# Interface.net
KiCad netlist of a schematic drawn in Altium Designer
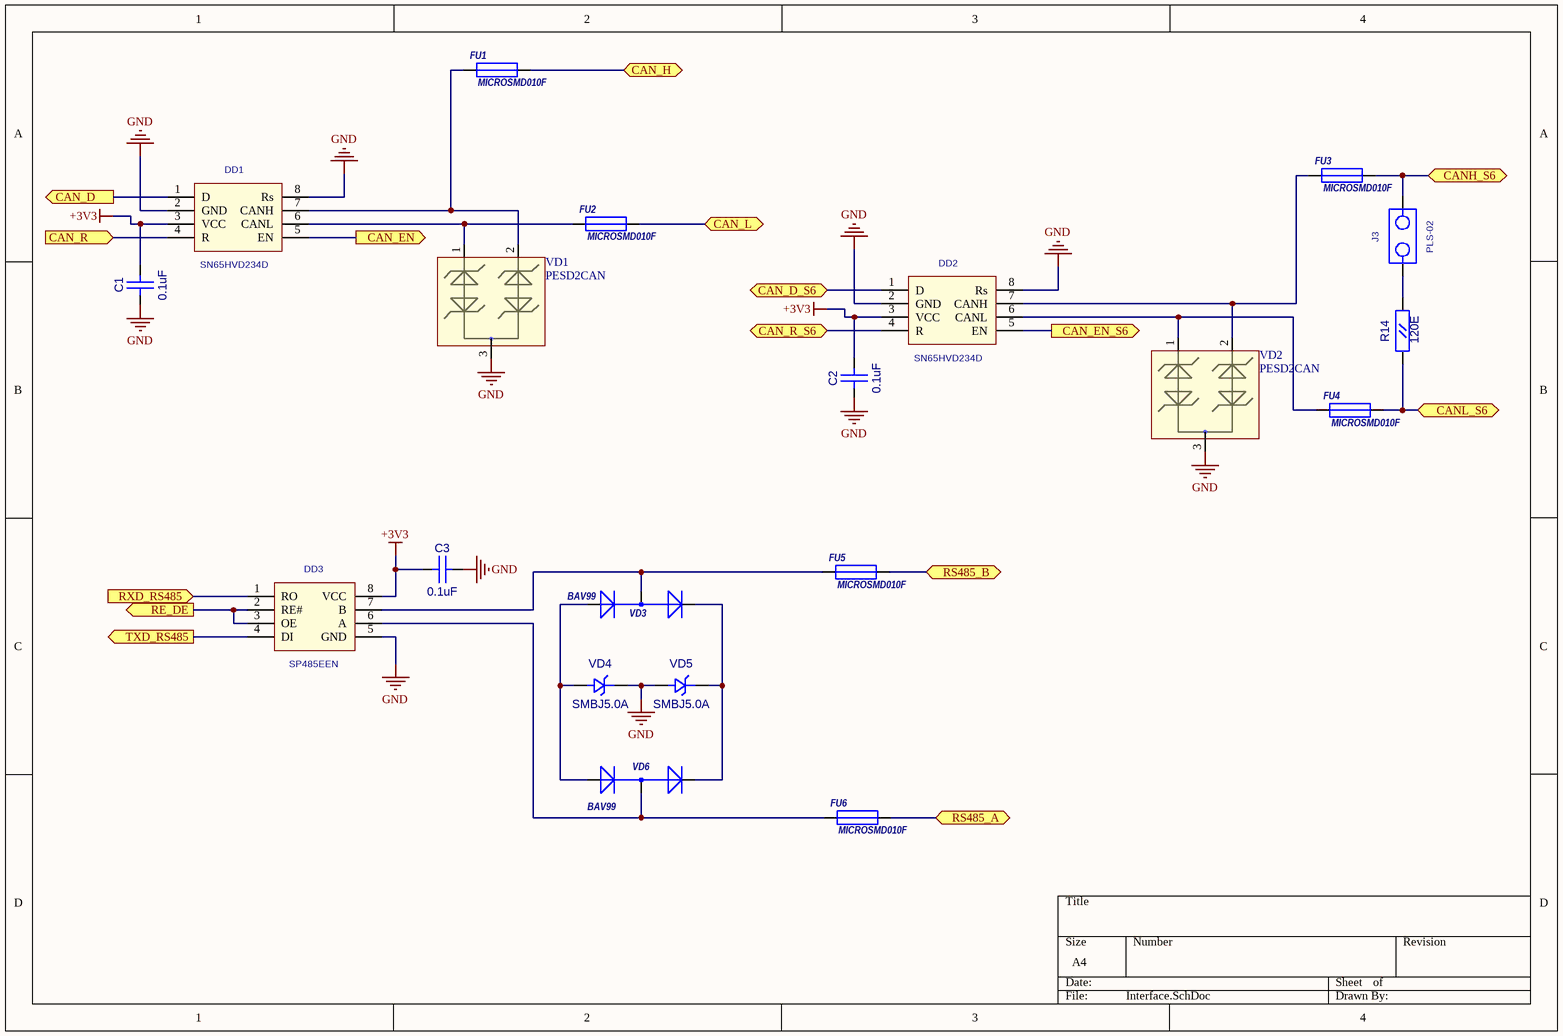
[diagram p0: Interface.SchDoc]

(export (version "E")
  (design (tool "Eeschema 10.0.6"))
  (components
    (comp (ref "C1")
      (value "0.1uF")
      (footprint "CC0603")
      (description "CC0603")
      (libsource (lib "gprs_modem_2") (part "CC0603"))
    )
    (comp (ref "C2")
      (value "0.1uF")
      (footprint "CC0603")
      (description "CC0603")
      (libsource (lib "gprs_modem_2") (part "CC0603"))
    )
    (comp (ref "C3")
      (value "0.1uF")
      (footprint "CC0603")
      (description "CC0603")
      (libsource (lib "gprs_modem_2") (part "CC0603"))
    )
    (comp (ref "DD1")
      (value "SN65HVD234D")
      (footprint "SO-8")
      (description "CAN Transceiver")
      (libsource (lib "gprs_modem_2") (part "SN65HVD234D"))
    )
    (comp (ref "DD2")
      (value "SN65HVD234D")
      (footprint "SO-8")
      (description "CAN Transceiver")
      (libsource (lib "gprs_modem_2") (part "SN65HVD234D"))
    )
    (comp (ref "DD3")
      (value "SP485EEN")
      (footprint "SO-8")
      (description "SP485")
      (libsource (lib "gprs_modem_2") (part "SP485"))
    )
    (comp (ref "FU1")
      (value "MICROSMD010F")
      (footprint "RC1210")
      (description "MICROSMD")
      (libsource (lib "gprs_modem_2") (part "MICROSMD"))
    )
    (comp (ref "FU2")
      (value "MICROSMD010F")
      (footprint "RC1210")
      (description "MICROSMD")
      (libsource (lib "gprs_modem_2") (part "MICROSMD"))
    )
    (comp (ref "FU3")
      (value "MICROSMD010F")
      (footprint "RC1210")
      (description "MICROSMD")
      (libsource (lib "gprs_modem_2") (part "MICROSMD"))
    )
    (comp (ref "FU4")
      (value "MICROSMD010F")
      (footprint "RC1210")
      (description "MICROSMD")
      (libsource (lib "gprs_modem_2") (part "MICROSMD"))
    )
    (comp (ref "FU5")
      (value "MICROSMD010F")
      (footprint "RC1210")
      (description "MICROSMD")
      (libsource (lib "gprs_modem_2") (part "MICROSMD"))
    )
    (comp (ref "FU6")
      (value "MICROSMD010F")
      (footprint "RC1210")
      (description "MICROSMD")
      (libsource (lib "gprs_modem_2") (part "MICROSMD"))
    )
    (comp (ref "J3") (value "PLS-02") (footprint "PLS-02") (libsource (lib "gprs_modem_2") (part "PLS-02")))
    (comp (ref "R14")
      (value "120E")
      (footprint "RC0805")
      (description "RC0805")
      (libsource (lib "gprs_modem_2") (part "RC0805"))
    )
    (comp (ref "VD1")
      (value "PESD2CAN")
      (footprint "SOT-23(123)")
      (description "TVS for CAN")
      (libsource (lib "gprs_modem_2") (part "PESD2CAN"))
    )
    (comp (ref "VD2")
      (value "PESD2CAN")
      (footprint "SOT-23(123)")
      (description "TVS for CAN")
      (libsource (lib "gprs_modem_2") (part "PESD2CAN"))
    )
    (comp (ref "VD3")
      (value "BAV99")
      (footprint "SOT-23(GSD)")
      (description "1.0 Ampere General Purpose Rectifier")
      (libsource (lib "gprs_modem_2") (part "BAV99"))
    )
    (comp (ref "VD4")
      (value "SMBJ5.0A")
      (footprint "SMB")
      (description "SMBJ")
      (libsource (lib "gprs_modem_2") (part "SMBJ"))
    )
    (comp (ref "VD5")
      (value "SMBJ5.0A")
      (footprint "SMB")
      (description "SMBJ")
      (libsource (lib "gprs_modem_2") (part "SMBJ"))
    )
    (comp (ref "VD6")
      (value "BAV99")
      (footprint "SOT-23(GSD)")
      (description "1.0 Ampere General Purpose Rectifier")
      (libsource (lib "gprs_modem_2") (part "BAV99"))
    )
  )
  (nets
    (net (code "1") (name "+3V3") (class "Default")
      (node (ref "C1") (pin "2") (pinfunction "B_2") (pintype "passive"))
      (node (ref "C2") (pin "2") (pinfunction "B_2") (pintype "passive"))
      (node (ref "C3") (pin "1") (pinfunction "A_1") (pintype "passive"))
      (node (ref "DD1") (pin "3") (pinfunction "VCC_3") (pintype "passive"))
      (node (ref "DD2") (pin "3") (pinfunction "VCC_3") (pintype "passive"))
      (node (ref "DD3") (pin "8") (pinfunction "VCC_8") (pintype "passive"))
    )
    (net (code "2") (name "/CANH_S6") (class "Default")
      (node (ref "FU3") (pin "2") (pintype "passive"))
      (node (ref "J3") (pin "2") (pintype "passive"))
    )
    (net (code "3") (name "/CANL_S6") (class "Default")
      (node (ref "FU4") (pin "2") (pintype "passive"))
      (node (ref "R14") (pin "1") (pinfunction "A_1") (pintype "passive"))
    )
    (net (code "4") (name "/CAN_D") (class "Default")
      (node (ref "DD1") (pin "1") (pinfunction "D_1") (pintype "passive"))
    )
    (net (code "5") (name "/CAN_D_S6") (class "Default")
      (node (ref "DD2") (pin "1") (pinfunction "D_1") (pintype "passive"))
    )
    (net (code "6") (name "/CAN_EN") (class "Default")
      (node (ref "DD1") (pin "5") (pinfunction "EN_5") (pintype "passive"))
    )
    (net (code "7") (name "/CAN_EN_S6") (class "Default")
      (node (ref "DD2") (pin "5") (pinfunction "EN_5") (pintype "passive"))
    )
    (net (code "8") (name "/CAN_H") (class "Default") (node (ref "FU1") (pin "2") (pintype "passive")))
    (net (code "9") (name "/CAN_L") (class "Default") (node (ref "FU2") (pin "2") (pintype "passive")))
    (net (code "10") (name "/CAN_R") (class "Default")
      (node (ref "DD1") (pin "4") (pinfunction "R_4") (pintype "passive"))
    )
    (net (code "11") (name "/CAN_R_S6") (class "Default")
      (node (ref "DD2") (pin "4") (pinfunction "R_4") (pintype "passive"))
    )
    (net (code "12") (name "/RE_DE") (class "Default")
      (node (ref "DD3") (pin "2") (pinfunction "RE#_2") (pintype "passive"))
      (node (ref "DD3") (pin "3") (pinfunction "OE_3") (pintype "passive"))
    )
    (net (code "13") (name "/RS485_A") (class "Default") (node (ref "FU6") (pin "2") (pintype "passive")))
    (net (code "14") (name "/RS485_B") (class "Default") (node (ref "FU5") (pin "2") (pintype "passive")))
    (net (code "15") (name "/RXD_RS485") (class "Default")
      (node (ref "DD3") (pin "1") (pinfunction "RO_1") (pintype "passive"))
    )
    (net (code "16") (name "/TXD_RS485") (class "Default")
      (node (ref "DD3") (pin "4") (pinfunction "DI_4") (pintype "passive"))
    )
    (net (code "17") (name "GND") (class "Default")
      (node (ref "C1") (pin "1") (pinfunction "A_1") (pintype "passive"))
      (node (ref "C2") (pin "1") (pinfunction "A_1") (pintype "passive"))
      (node (ref "C3") (pin "2") (pinfunction "B_2") (pintype "passive"))
      (node (ref "DD1") (pin "2") (pinfunction "GND_2") (pintype "passive"))
      (node (ref "DD1") (pin "8") (pinfunction "Rs_8") (pintype "passive"))
      (node (ref "DD2") (pin "2") (pinfunction "GND_2") (pintype "passive"))
      (node (ref "DD2") (pin "8") (pinfunction "Rs_8") (pintype "passive"))
      (node (ref "DD3") (pin "5") (pinfunction "GND_5") (pintype "passive"))
      (node (ref "VD1") (pin "3") (pinfunction "3_3") (pintype "passive"))
      (node (ref "VD2") (pin "3") (pinfunction "3_3") (pintype "passive"))
      (node (ref "VD4") (pin "2") (pinfunction "K_2") (pintype "passive"))
      (node (ref "VD5") (pin "1") (pinfunction "A_1") (pintype "passive"))
    )
    (net (code "18") (name "Net-(DD1-CANH)") (class "Default")
      (node (ref "DD1") (pin "7") (pinfunction "CANH_7") (pintype "passive"))
      (node (ref "FU1") (pin "1") (pintype "passive"))
      (node (ref "VD1") (pin "2") (pinfunction "2_2") (pintype "passive"))
    )
    (net (code "19") (name "Net-(DD1-CANL)") (class "Default")
      (node (ref "DD1") (pin "6") (pinfunction "CANL_6") (pintype "passive"))
      (node (ref "FU2") (pin "1") (pintype "passive"))
      (node (ref "VD1") (pin "1") (pinfunction "1_1") (pintype "passive"))
    )
    (net (code "20") (name "Net-(DD2-CANH)") (class "Default")
      (node (ref "DD2") (pin "7") (pinfunction "CANH_7") (pintype "passive"))
      (node (ref "FU3") (pin "1") (pintype "passive"))
      (node (ref "VD2") (pin "2") (pinfunction "2_2") (pintype "passive"))
    )
    (net (code "21") (name "Net-(DD2-CANL)") (class "Default")
      (node (ref "DD2") (pin "6") (pinfunction "CANL_6") (pintype "passive"))
      (node (ref "FU4") (pin "1") (pintype "passive"))
      (node (ref "VD2") (pin "1") (pinfunction "1_1") (pintype "passive"))
    )
    (net (code "22") (name "Net-(DD3-A)") (class "Default")
      (node (ref "DD3") (pin "6") (pinfunction "A_6") (pintype "passive"))
      (node (ref "FU6") (pin "1") (pintype "passive"))
      (node (ref "VD6") (pin "3") (pinfunction "AK_3") (pintype "passive"))
    )
    (net (code "23") (name "Net-(DD3-B)") (class "Default")
      (node (ref "DD3") (pin "7") (pinfunction "B_7") (pintype "passive"))
      (node (ref "FU5") (pin "1") (pintype "passive"))
      (node (ref "VD3") (pin "3") (pinfunction "AK_3") (pintype "passive"))
    )
    (net (code "24") (name "Net-(R14-B)") (class "Default")
      (node (ref "J3") (pin "1") (pintype "passive"))
      (node (ref "R14") (pin "2") (pinfunction "B_2") (pintype "passive"))
    )
    (net (code "25") (name "Net-(VD3-A)") (class "Default")
      (node (ref "VD3") (pin "1") (pinfunction "A_1") (pintype "passive"))
      (node (ref "VD4") (pin "1") (pinfunction "A_1") (pintype "passive"))
      (node (ref "VD6") (pin "1") (pinfunction "A_1") (pintype "passive"))
    )
    (net (code "26") (name "Net-(VD3-K)") (class "Default")
      (node (ref "VD3") (pin "2") (pinfunction "K_2") (pintype "passive"))
      (node (ref "VD5") (pin "2") (pinfunction "K_2") (pintype "passive"))
      (node (ref "VD6") (pin "2") (pinfunction "K_2") (pintype "passive"))
    )
  )
)
